# mahirAMPLIFER.net
KiCad netlist of a schematic drawn in Altium Designer
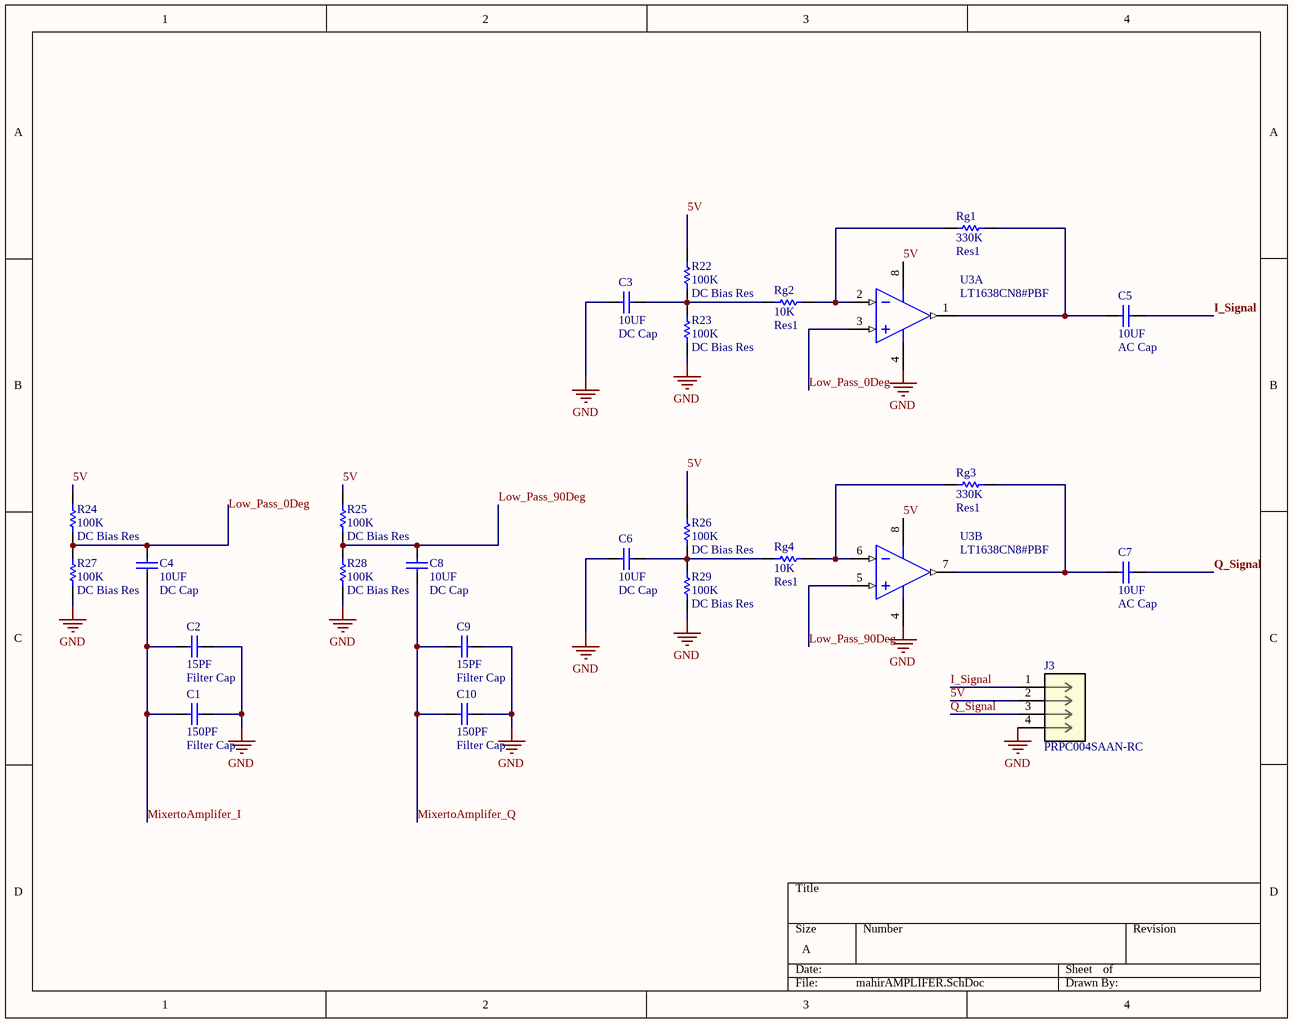
[diagram p0: mahirAMPLIFER.SchDoc]

(export (version "E")
  (design (tool "Eeschema 10.0.6"))
  (components
    (comp (ref "C1")
      (value "Filter Cap")
      (footprint "RADIAL-0.1")
      (description "Capacitor")
      (fields
        (field (name "ALTIUM_VALUE") "150PF")
        (field (name "MANUFACTURER PART NUMBER") "K151J15C0GF53L2")
        (field (name "PUBLISHER") "Altium Limited")
      )
      (libsource (lib "ECE295-Capacitors-TH") (part "CAP CER 150PF 50V C0G/NP0 RADIAL"))
    )
    (comp (ref "C2")
      (value "Filter Cap")
      (footprint "RADIAL-0.1")
      (description "Capacitor")
      (fields
        (field (name "ALTIUM_VALUE") "15PF")
        (field (name "MANUFACTURER PART NUMBER") "K150J15C0GF5TL2")
        (field (name "PUBLISHER") "Altium Limited")
      )
      (libsource (lib "ECE295-Capacitors-TH") (part "CAP CER 15PF 50V C0G/NP0 RADIAL"))
    )
    (comp (ref "C3")
      (value "DC Cap")
      (footprint "RADIAL-0.1")
      (description "Capacitor")
      (fields
        (field (name "ALTIUM_VALUE") "10UF")
        (field (name "MANUFACTURER PART NUMBER") "ESK106M063AC3FA")
        (field (name "PUBLISHER") "Altium Limited")
      )
      (libsource (lib "ECE295-Capacitors-TH") (part "CAP ALUM 10UF 20% 63V RADIAL"))
    )
    (comp (ref "C4")
      (value "DC Cap")
      (footprint "RADIAL-0.1")
      (description "Capacitor")
      (fields
        (field (name "ALTIUM_VALUE") "10UF")
        (field (name "MANUFACTURER PART NUMBER") "ESK106M063AC3FA")
        (field (name "PUBLISHER") "Altium Limited")
      )
      (libsource (lib "ECE295-Capacitors-TH") (part "CAP ALUM 10UF 20% 63V RADIAL"))
    )
    (comp (ref "C5")
      (value "AC Cap")
      (footprint "RADIAL-0.1")
      (description "Capacitor")
      (fields
        (field (name "ALTIUM_VALUE") "10UF")
        (field (name "MANUFACTURER PART NUMBER") "ESK106M063AC3FA")
        (field (name "PUBLISHER") "Altium Limited")
      )
      (libsource (lib "ECE295-Capacitors-TH") (part "CAP ALUM 10UF 20% 63V RADIAL"))
    )
    (comp (ref "C6")
      (value "DC Cap")
      (footprint "RADIAL-0.1")
      (description "Capacitor")
      (fields
        (field (name "ALTIUM_VALUE") "10UF")
        (field (name "MANUFACTURER PART NUMBER") "ESK106M063AC3FA")
        (field (name "PUBLISHER") "Altium Limited")
      )
      (libsource (lib "ECE295-Capacitors-TH") (part "CAP ALUM 10UF 20% 63V RADIAL"))
    )
    (comp (ref "C7")
      (value "AC Cap")
      (footprint "RADIAL-0.1")
      (description "Capacitor")
      (fields
        (field (name "ALTIUM_VALUE") "10UF")
        (field (name "MANUFACTURER PART NUMBER") "ESK106M063AC3FA")
        (field (name "PUBLISHER") "Altium Limited")
      )
      (libsource (lib "ECE295-Capacitors-TH") (part "CAP ALUM 10UF 20% 63V RADIAL"))
    )
    (comp (ref "C8")
      (value "DC Cap")
      (footprint "RADIAL-0.1")
      (description "Capacitor")
      (fields
        (field (name "ALTIUM_VALUE") "10UF")
        (field (name "MANUFACTURER PART NUMBER") "ESK106M063AC3FA")
        (field (name "PUBLISHER") "Altium Limited")
      )
      (libsource (lib "ECE295-Capacitors-TH") (part "CAP ALUM 10UF 20% 63V RADIAL"))
    )
    (comp (ref "C9")
      (value "Filter Cap")
      (footprint "RADIAL-0.1")
      (description "Capacitor")
      (fields
        (field (name "ALTIUM_VALUE") "15PF")
        (field (name "MANUFACTURER PART NUMBER") "K150J15C0GF5TL2")
        (field (name "PUBLISHER") "Altium Limited")
      )
      (libsource (lib "ECE295-Capacitors-TH") (part "CAP CER 15PF 50V C0G/NP0 RADIAL"))
    )
    (comp (ref "C10")
      (value "Filter Cap")
      (footprint "RADIAL-0.1")
      (description "Capacitor")
      (fields
        (field (name "ALTIUM_VALUE") "150PF")
        (field (name "MANUFACTURER PART NUMBER") "K151J15C0GF53L2")
        (field (name "PUBLISHER") "Altium Limited")
      )
      (libsource (lib "ECE295-Capacitors-TH") (part "CAP CER 150PF 50V C0G/NP0 RADIAL"))
    )
    (comp (ref "J3")
      (value "PRPC004SAAN-RC")
      (footprint "CONN4_PRPC004_SUL")
      (description "No Description Available")
      (libsource (lib "PRPC004SAAN-RC") (part "PRPC004SAAN-RC"))
    )
    (comp (ref "R22")
      (value "DC Bias Res")
      (footprint "AXIAL-0.1-RES")
      (description "Resistor")
      (fields
        (field (name "ALTIUM_VALUE") "100K")
        (field (name "MANUFACTURER PART NUMBER") "CFR-25JB-52-100K")
        (field (name "TOLERANCE") "0.05")
        (field (name "PUBLISHER") "Altium Limited")
      )
      (libsource (lib "ECE295-Resistors-TH") (part "RES 100K OHM 5% 1/4W AXIAL"))
    )
    (comp (ref "R23")
      (value "DC Bias Res")
      (footprint "AXIAL-0.1-RES")
      (description "Resistor")
      (fields
        (field (name "ALTIUM_VALUE") "100K")
        (field (name "MANUFACTURER PART NUMBER") "CFR-25JB-52-100K")
        (field (name "TOLERANCE") "0.05")
        (field (name "PUBLISHER") "Altium Limited")
      )
      (libsource (lib "ECE295-Resistors-TH") (part "RES 100K OHM 5% 1/4W AXIAL"))
    )
    (comp (ref "R24")
      (value "DC Bias Res")
      (footprint "AXIAL-0.1-RES")
      (description "Resistor")
      (fields
        (field (name "ALTIUM_VALUE") "100K")
        (field (name "MANUFACTURER PART NUMBER") "CFR-25JB-52-100K")
        (field (name "TOLERANCE") "0.05")
        (field (name "PUBLISHER") "Altium Limited")
      )
      (libsource (lib "ECE295-Resistors-TH") (part "RES 100K OHM 5% 1/4W AXIAL"))
    )
    (comp (ref "R25")
      (value "DC Bias Res")
      (footprint "AXIAL-0.1-RES")
      (description "Resistor")
      (fields
        (field (name "ALTIUM_VALUE") "100K")
        (field (name "MANUFACTURER PART NUMBER") "CFR-25JB-52-100K")
        (field (name "TOLERANCE") "0.05")
        (field (name "PUBLISHER") "Altium Limited")
      )
      (libsource (lib "ECE295-Resistors-TH") (part "RES 100K OHM 5% 1/4W AXIAL"))
    )
    (comp (ref "R26")
      (value "DC Bias Res")
      (footprint "AXIAL-0.1-RES")
      (description "Resistor")
      (fields
        (field (name "ALTIUM_VALUE") "100K")
        (field (name "MANUFACTURER PART NUMBER") "CFR-25JB-52-100K")
        (field (name "TOLERANCE") "0.05")
        (field (name "PUBLISHER") "Altium Limited")
      )
      (libsource (lib "ECE295-Resistors-TH") (part "RES 100K OHM 5% 1/4W AXIAL"))
    )
    (comp (ref "R27")
      (value "DC Bias Res")
      (footprint "AXIAL-0.1-RES")
      (description "Resistor")
      (fields
        (field (name "ALTIUM_VALUE") "100K")
        (field (name "MANUFACTURER PART NUMBER") "CFR-25JB-52-100K")
        (field (name "TOLERANCE") "0.05")
        (field (name "PUBLISHER") "Altium Limited")
      )
      (libsource (lib "ECE295-Resistors-TH") (part "RES 100K OHM 5% 1/4W AXIAL"))
    )
    (comp (ref "R28")
      (value "DC Bias Res")
      (footprint "AXIAL-0.1-RES")
      (description "Resistor")
      (fields
        (field (name "ALTIUM_VALUE") "100K")
        (field (name "MANUFACTURER PART NUMBER") "CFR-25JB-52-100K")
        (field (name "TOLERANCE") "0.05")
        (field (name "PUBLISHER") "Altium Limited")
      )
      (libsource (lib "ECE295-Resistors-TH") (part "RES 100K OHM 5% 1/4W AXIAL"))
    )
    (comp (ref "R29")
      (value "DC Bias Res")
      (footprint "AXIAL-0.1-RES")
      (description "Resistor")
      (fields
        (field (name "ALTIUM_VALUE") "100K")
        (field (name "MANUFACTURER PART NUMBER") "CFR-25JB-52-100K")
        (field (name "TOLERANCE") "0.05")
        (field (name "PUBLISHER") "Altium Limited")
      )
      (libsource (lib "ECE295-Resistors-TH") (part "RES 100K OHM 5% 1/4W AXIAL"))
    )
    (comp (ref "Rg1")
      (value "Res1")
      (footprint "AXIAL-0.1-RES")
      (description "Resistor")
      (fields
        (field (name "ALTIUM_VALUE") "330K")
        (field (name "MANUFACTURER PART NUMBER") "CFR-25JB-52-330K")
        (field (name "TOLERANCE") "0.05")
        (field (name "PUBLISHER") "Altium Limited")
      )
      (libsource (lib "ECE295-Resistors-TH") (part "RES 330K OHM 5% 1/4W AXIAL"))
    )
    (comp (ref "Rg2")
      (value "Res1")
      (footprint "AXIAL-0.1-RES")
      (description "Resistor")
      (fields
        (field (name "ALTIUM_VALUE") "10K")
        (field (name "MANUFACTURER PART NUMBER") "CFR-25JB-52-10K")
        (field (name "TOLERANCE") "0.05")
        (field (name "PUBLISHER") "Altium Limited")
      )
      (libsource (lib "ECE295-Resistors-TH") (part "RES 10K OHM 5% 1/4W AXIAL"))
    )
    (comp (ref "Rg3")
      (value "Res1")
      (footprint "AXIAL-0.1-RES")
      (description "Resistor")
      (fields
        (field (name "ALTIUM_VALUE") "330K")
        (field (name "MANUFACTURER PART NUMBER") "CFR-25JB-52-330K")
        (field (name "TOLERANCE") "0.05")
        (field (name "PUBLISHER") "Altium Limited")
      )
      (libsource (lib "ECE295-Resistors-TH") (part "RES 330K OHM 5% 1/4W AXIAL"))
    )
    (comp (ref "Rg4")
      (value "Res1")
      (footprint "AXIAL-0.1-RES")
      (description "Resistor")
      (fields
        (field (name "ALTIUM_VALUE") "10K")
        (field (name "MANUFACTURER PART NUMBER") "CFR-25JB-52-10K")
        (field (name "TOLERANCE") "0.05")
        (field (name "PUBLISHER") "Altium Limited")
      )
      (libsource (lib "ECE295-Resistors-TH") (part "RES 10K OHM 5% 1/4W AXIAL"))
    )
    (comp (ref "U3")
      (value "LT1638CN8#PBF")
      (footprint "LT-N8-8")
      (fields
        (field (name "MANUFACTURER") "Linear Technology")
        (field (name "LINEAR TECHNOLOGY PART NUMBER") "LT1638")
      )
      (libsource (lib "Altium Content Vault") (part "LT-LT1638-N8-8"))
    )
  )
  (nets
    (net (code "1") (name "/5V") (class "Default")
      (node (ref "J3") (pin "2") (pinfunction "2_2") (pintype "passive"))
      (node (ref "R22") (pin "2") (pinfunction "2_2") (pintype "passive"))
      (node (ref "R24") (pin "2") (pinfunction "2_2") (pintype "passive"))
      (node (ref "R25") (pin "2") (pinfunction "2_2") (pintype "passive"))
      (node (ref "R26") (pin "2") (pinfunction "2_2") (pintype "passive"))
      (node (ref "U3") (pin "8") (pinfunction "V+_8") (pintype "power_in"))
    )
    (net (code "2") (name "/I_Signal") (class "Default")
      (node (ref "C5") (pin "1") (pinfunction "1_1") (pintype "passive"))
      (node (ref "J3") (pin "1") (pinfunction "1_1") (pintype "passive"))
    )
    (net (code "3") (name "/Low_Pass_0Deg") (class "Default")
      (node (ref "C4") (pin "2") (pinfunction "2_2") (pintype "passive"))
      (node (ref "R24") (pin "1") (pinfunction "1_1") (pintype "passive"))
      (node (ref "R27") (pin "2") (pinfunction "2_2") (pintype "passive"))
      (node (ref "U3") (pin "3") (pinfunction "+IN_A_3") (pintype "input"))
    )
    (net (code "4") (name "/Low_Pass_90Deg") (class "Default")
      (node (ref "C8") (pin "2") (pinfunction "2_2") (pintype "passive"))
      (node (ref "R25") (pin "1") (pinfunction "1_1") (pintype "passive"))
      (node (ref "R28") (pin "2") (pinfunction "2_2") (pintype "passive"))
      (node (ref "U3") (pin "5") (pinfunction "+IN_B_5") (pintype "input"))
    )
    (net (code "5") (name "/MixertoAmplifer_I") (class "Default")
      (node (ref "C1") (pin "1") (pinfunction "1_1") (pintype "passive"))
      (node (ref "C2") (pin "1") (pinfunction "1_1") (pintype "passive"))
      (node (ref "C4") (pin "1") (pinfunction "1_1") (pintype "passive"))
    )
    (net (code "6") (name "/MixertoAmplifer_Q") (class "Default")
      (node (ref "C10") (pin "1") (pinfunction "1_1") (pintype "passive"))
      (node (ref "C8") (pin "1") (pinfunction "1_1") (pintype "passive"))
      (node (ref "C9") (pin "1") (pinfunction "1_1") (pintype "passive"))
    )
    (net (code "7") (name "/Q_Signal") (class "Default")
      (node (ref "C7") (pin "1") (pinfunction "1_1") (pintype "passive"))
      (node (ref "J3") (pin "3") (pinfunction "3_3") (pintype "passive"))
    )
    (net (code "8") (name "GND") (class "Default")
      (node (ref "C1") (pin "2") (pinfunction "2_2") (pintype "passive"))
      (node (ref "C10") (pin "2") (pinfunction "2_2") (pintype "passive"))
      (node (ref "C2") (pin "2") (pinfunction "2_2") (pintype "passive"))
      (node (ref "C3") (pin "2") (pinfunction "2_2") (pintype "passive"))
      (node (ref "C6") (pin "2") (pinfunction "2_2") (pintype "passive"))
      (node (ref "C9") (pin "2") (pinfunction "2_2") (pintype "passive"))
      (node (ref "J3") (pin "4") (pinfunction "4_4") (pintype "passive"))
      (node (ref "R23") (pin "1") (pinfunction "1_1") (pintype "passive"))
      (node (ref "R27") (pin "1") (pinfunction "1_1") (pintype "passive"))
      (node (ref "R28") (pin "1") (pinfunction "1_1") (pintype "passive"))
      (node (ref "R29") (pin "1") (pinfunction "1_1") (pintype "passive"))
      (node (ref "U3") (pin "4") (pinfunction "V-_4") (pintype "power_in"))
    )
    (net (code "9") (name "Net-(C3-Pad1)") (class "Default")
      (node (ref "C3") (pin "1") (pinfunction "1_1") (pintype "passive"))
      (node (ref "R22") (pin "1") (pinfunction "1_1") (pintype "passive"))
      (node (ref "R23") (pin "2") (pinfunction "2_2") (pintype "passive"))
      (node (ref "Rg2") (pin "1") (pinfunction "1_1") (pintype "passive"))
    )
    (net (code "10") (name "Net-(C6-Pad1)") (class "Default")
      (node (ref "C6") (pin "1") (pinfunction "1_1") (pintype "passive"))
      (node (ref "R26") (pin "1") (pinfunction "1_1") (pintype "passive"))
      (node (ref "R29") (pin "2") (pinfunction "2_2") (pintype "passive"))
      (node (ref "Rg4") (pin "1") (pinfunction "1_1") (pintype "passive"))
    )
    (net (code "11") (name "Net-(U3A--IN_A)") (class "Default")
      (node (ref "Rg1") (pin "1") (pinfunction "1_1") (pintype "passive"))
      (node (ref "Rg2") (pin "2") (pinfunction "2_2") (pintype "passive"))
      (node (ref "U3") (pin "2") (pinfunction "-IN_A_2") (pintype "input"))
    )
    (net (code "12") (name "Net-(U3A-OUT_A)") (class "Default")
      (node (ref "C5") (pin "2") (pinfunction "2_2") (pintype "passive"))
      (node (ref "Rg1") (pin "2") (pinfunction "2_2") (pintype "passive"))
      (node (ref "U3") (pin "1") (pinfunction "OUT_A_1") (pintype "output"))
    )
    (net (code "13") (name "Net-(U3B--IN_B)") (class "Default")
      (node (ref "Rg3") (pin "1") (pinfunction "1_1") (pintype "passive"))
      (node (ref "Rg4") (pin "2") (pinfunction "2_2") (pintype "passive"))
      (node (ref "U3") (pin "6") (pinfunction "-IN_B_6") (pintype "input"))
    )
    (net (code "14") (name "Net-(U3B-OUT_B)") (class "Default")
      (node (ref "C7") (pin "2") (pinfunction "2_2") (pintype "passive"))
      (node (ref "Rg3") (pin "2") (pinfunction "2_2") (pintype "passive"))
      (node (ref "U3") (pin "7") (pinfunction "OUT_B_7") (pintype "output"))
    )
  )
)
